# irisc.net
KiCad netlist of a schematic drawn in EAGLE
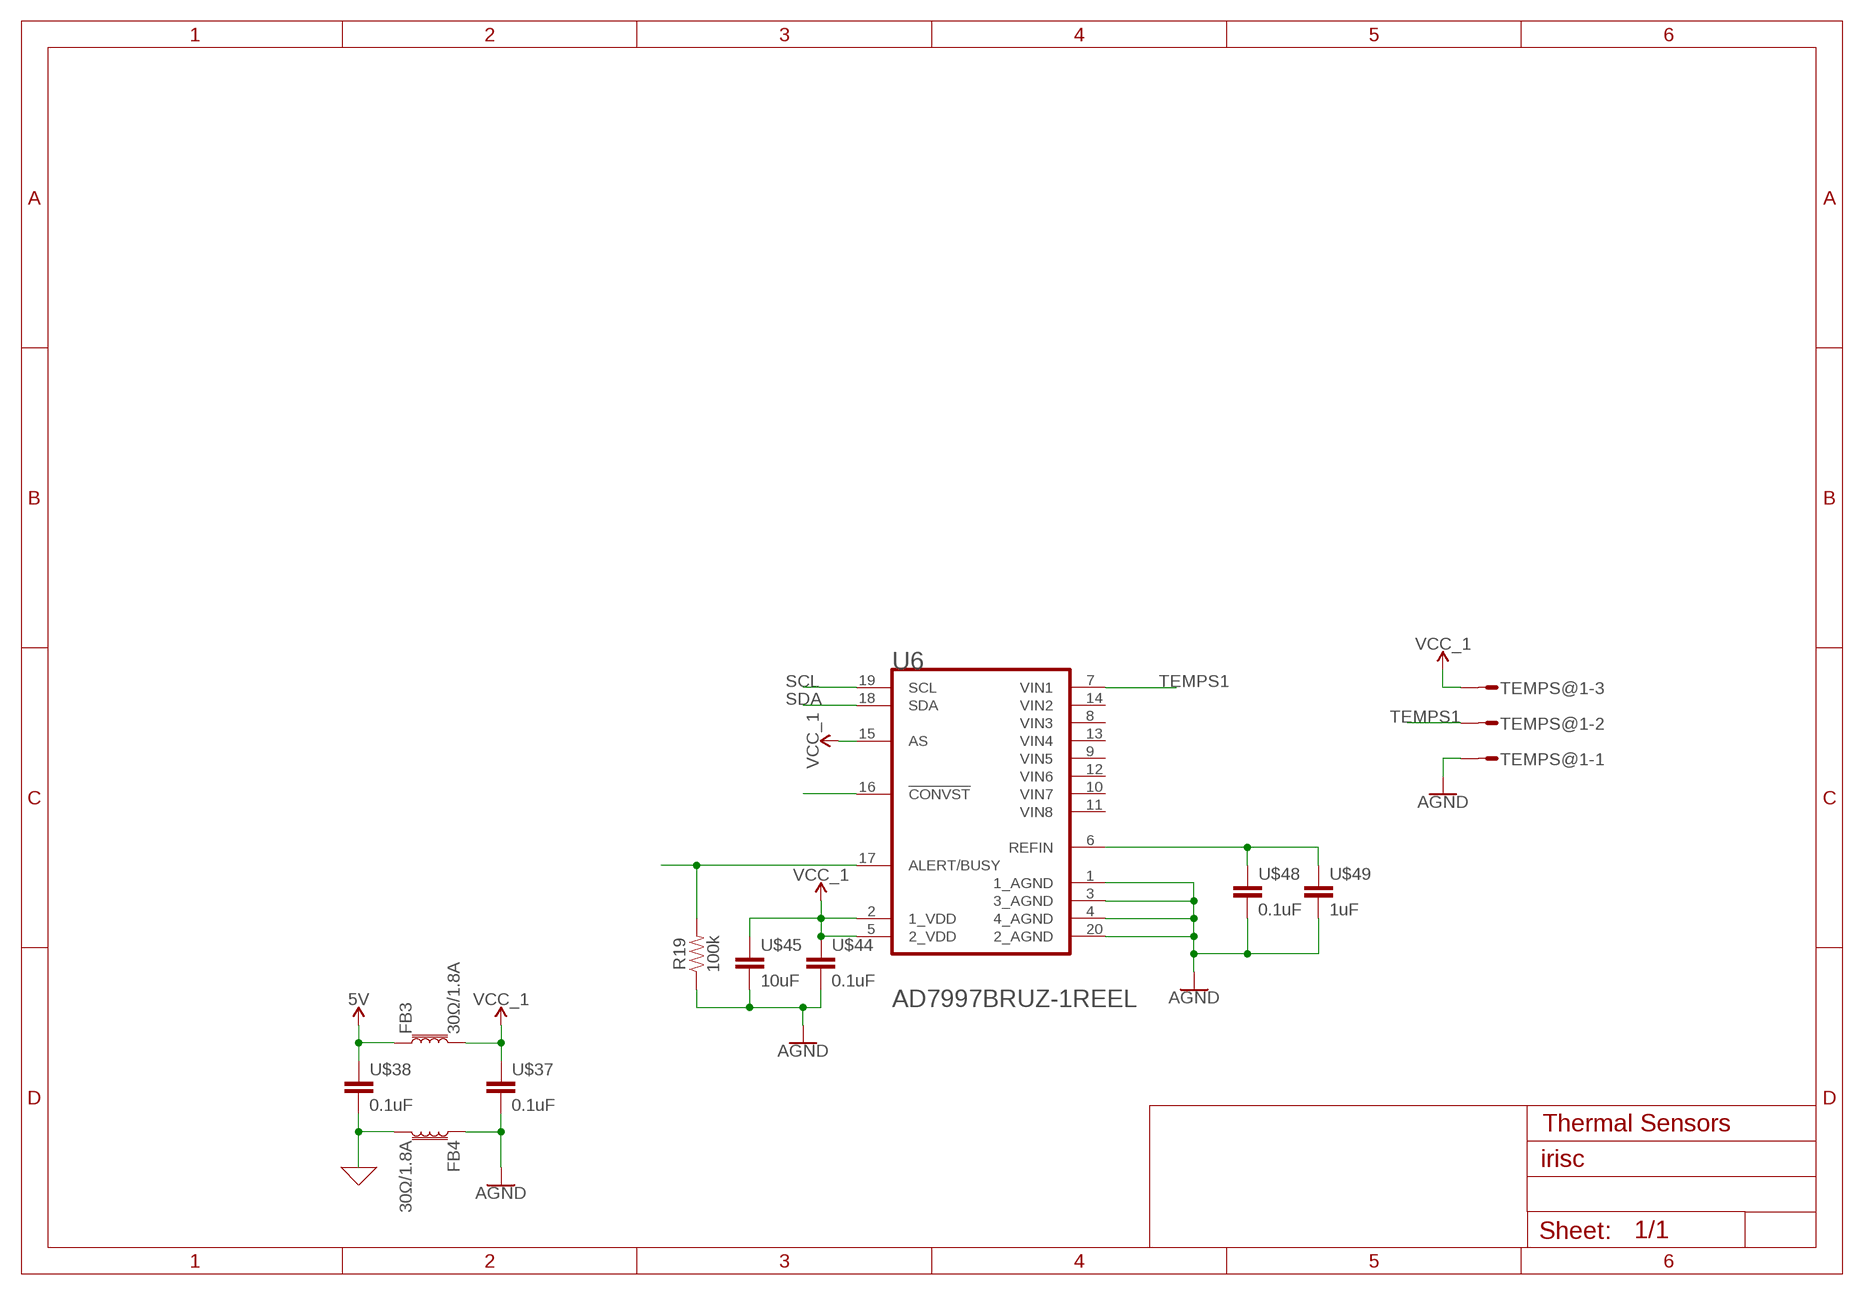
[diagram p0: schematic, sheet 1]

(export (version "E")
  (design (tool "Eeschema 10.0.6"))
  (components
    (comp (ref "FB3")
      (value "30Ω/1.8A")
      (footprint "eagle-import:0603")
      (libsource (lib "eagle-import") (part "FERRITE_BEAD-0603"))
    )
    (comp (ref "FB4")
      (value "30Ω/1.8A")
      (footprint "eagle-import:0603")
      (libsource (lib "eagle-import") (part "FERRITE_BEAD-0603"))
    )
    (comp (ref "R19")
      (value "100k")
      (footprint "eagle-import:0603")
      (libsource (lib "eagle-import") (part "100KOHM-0603-1/10W-1%"))
    )
    (comp (ref "TEMPS@1")
      (value "L03P")
      (footprint "eagle-import:L03P")
      (libsource (lib "eagle-import") (part "L03P"))
    )
    (comp (ref "U$37")
      (value "0.1uF")
      (footprint "eagle-import:RESC0603_N")
      (libsource (lib "eagle-import") (part "CAPACITOR_0603_N"))
    )
    (comp (ref "U$38")
      (value "0.1uF")
      (footprint "eagle-import:RESC0603_N")
      (libsource (lib "eagle-import") (part "CAPACITOR_0603_N"))
    )
    (comp (ref "U$44")
      (value "0.1uF")
      (footprint "eagle-import:RESC0603_N")
      (libsource (lib "eagle-import") (part "CAPACITOR_0603_N"))
    )
    (comp (ref "U$45")
      (value "10uF")
      (footprint "eagle-import:RESC0805_L")
      (libsource (lib "eagle-import") (part "CAPACITOR_0805_L"))
    )
    (comp (ref "U$48")
      (value "0.1uF")
      (footprint "eagle-import:RESC0603_N")
      (libsource (lib "eagle-import") (part "CAPACITOR_0603_N"))
    )
    (comp (ref "U$49")
      (value "1uF")
      (footprint "eagle-import:RESC0603_N")
      (libsource (lib "eagle-import") (part "CAPACITOR_0603_N"))
    )
    (comp (ref "U6")
      (value "ANALOG_DEVICES_AD7997BRUZ-1REELANALOG_DEVICES_AD7997BRUZ-1REEL_0_0")
      (footprint "eagle-import:ANALOG_DEVICES_AD7997BRUZ-1REEL_0")
      (fields (field (name "MF") "Analog Devices") (field (name "MPN") "AD7997BRUZ-1REEL"))
      (libsource (lib "eagle-import") (part "ANALOG_DEVICES_AD7997BRUZ-1REELANALOG_DEVICES_AD7997BRUZ-1REEL_0_0"))
    )
  )
  (nets
    (net (code "1") (name "/SCL") (class "Default")
      (node (ref "U6") (pin "19") (pinfunction "SCL_19") (pintype "input"))
    )
    (net (code "2") (name "/SDA") (class "Default")
      (node (ref "U6") (pin "18") (pinfunction "SDA_18") (pintype "bidirectional"))
    )
    (net (code "3") (name "/TEMPS1") (class "Default")
      (node (ref "TEMPS@1") (pin "2") (pinfunction "S_2") (pintype "passive"))
      (node (ref "U6") (pin "7") (pinfunction "VIN1_7") (pintype "input"))
    )
    (net (code "4") (name "5V") (class "Default")
      (node (ref "FB3") (pin "1") (pinfunction "1_1") (pintype "passive"))
      (node (ref "U$38") (pin "1") (pinfunction "1_1") (pintype "passive"))
    )
    (net (code "5") (name "AGND") (class "Default")
      (node (ref "FB4") (pin "1") (pinfunction "1_1") (pintype "passive"))
      (node (ref "R19") (pin "1") (pinfunction "1_1") (pintype "passive"))
      (node (ref "TEMPS@1") (pin "1") (pinfunction "S_1") (pintype "passive"))
      (node (ref "U$37") (pin "2") (pinfunction "2_2") (pintype "passive"))
      (node (ref "U$44") (pin "2") (pinfunction "2_2") (pintype "passive"))
      (node (ref "U$45") (pin "2") (pinfunction "2_2") (pintype "passive"))
      (node (ref "U$48") (pin "2") (pinfunction "2_2") (pintype "passive"))
      (node (ref "U$49") (pin "2") (pinfunction "2_2") (pintype "passive"))
      (node (ref "U6") (pin "1") (pinfunction "1_AGND_1") (pintype "power_in"))
      (node (ref "U6") (pin "20") (pinfunction "2_AGND_20") (pintype "power_in"))
      (node (ref "U6") (pin "3") (pinfunction "3_AGND_3") (pintype "power_in"))
      (node (ref "U6") (pin "4") (pinfunction "4_AGND_4") (pintype "power_in"))
    )
    (net (code "6") (name "GND") (class "Default")
      (node (ref "FB4") (pin "2") (pinfunction "2_2") (pintype "passive"))
      (node (ref "U$38") (pin "2") (pinfunction "2_2") (pintype "passive"))
    )
    (net (code "7") (name "Net-(U6-ALERT{slash}BUSY)") (class "Default")
      (node (ref "R19") (pin "2") (pinfunction "2_2") (pintype "passive"))
      (node (ref "U6") (pin "17") (pinfunction "ALERT/BUSY_17") (pintype "open_collector"))
    )
    (net (code "8") (name "Net-(U6-REFIN)") (class "Default")
      (node (ref "U$48") (pin "1") (pinfunction "1_1") (pintype "passive"))
      (node (ref "U$49") (pin "1") (pinfunction "1_1") (pintype "passive"))
      (node (ref "U6") (pin "6") (pinfunction "REFIN_6") (pintype "input"))
    )
    (net (code "9") (name "VCC_1") (class "Default")
      (node (ref "FB3") (pin "2") (pinfunction "2_2") (pintype "passive"))
      (node (ref "TEMPS@1") (pin "3") (pinfunction "S_3") (pintype "passive"))
      (node (ref "U$37") (pin "1") (pinfunction "1_1") (pintype "passive"))
      (node (ref "U$44") (pin "1") (pinfunction "1_1") (pintype "passive"))
      (node (ref "U$45") (pin "1") (pinfunction "1_1") (pintype "passive"))
      (node (ref "U6") (pin "15") (pinfunction "AS_15") (pintype "input"))
      (node (ref "U6") (pin "2") (pinfunction "1_VDD_2") (pintype "power_in"))
      (node (ref "U6") (pin "5") (pinfunction "2_VDD_5") (pintype "power_in"))
    )
    (net (code "10") (name "unconnected-(U6-VIN2-Pad14)") (class "Default")
      (node (ref "U6") (pin "14") (pinfunction "VIN2_14") (pintype "input"))
    )
    (net (code "11") (name "unconnected-(U6-VIN3-Pad8)") (class "Default")
      (node (ref "U6") (pin "8") (pinfunction "VIN3_8") (pintype "input"))
    )
    (net (code "12") (name "unconnected-(U6-VIN4-Pad13)") (class "Default")
      (node (ref "U6") (pin "13") (pinfunction "VIN4_13") (pintype "input"))
    )
    (net (code "13") (name "unconnected-(U6-VIN5-Pad9)") (class "Default")
      (node (ref "U6") (pin "9") (pinfunction "VIN5_9") (pintype "input"))
    )
    (net (code "14") (name "unconnected-(U6-VIN6-Pad12)") (class "Default")
      (node (ref "U6") (pin "12") (pinfunction "VIN6_12") (pintype "input"))
    )
    (net (code "15") (name "unconnected-(U6-VIN7-Pad10)") (class "Default")
      (node (ref "U6") (pin "10") (pinfunction "VIN7_10") (pintype "input"))
    )
    (net (code "16") (name "unconnected-(U6-VIN8-Pad11)") (class "Default")
      (node (ref "U6") (pin "11") (pinfunction "VIN8_11") (pintype "input"))
    )
    (net (code "17") (name "unconnected-(U6-~{CONVST}-Pad16)") (class "Default")
      (node (ref "U6") (pin "16") (pinfunction "~{CONVST}_16") (pintype "input"))
    )
  )
)
